# Main_board.net
KiCad netlist of a schematic drawn in EAGLE
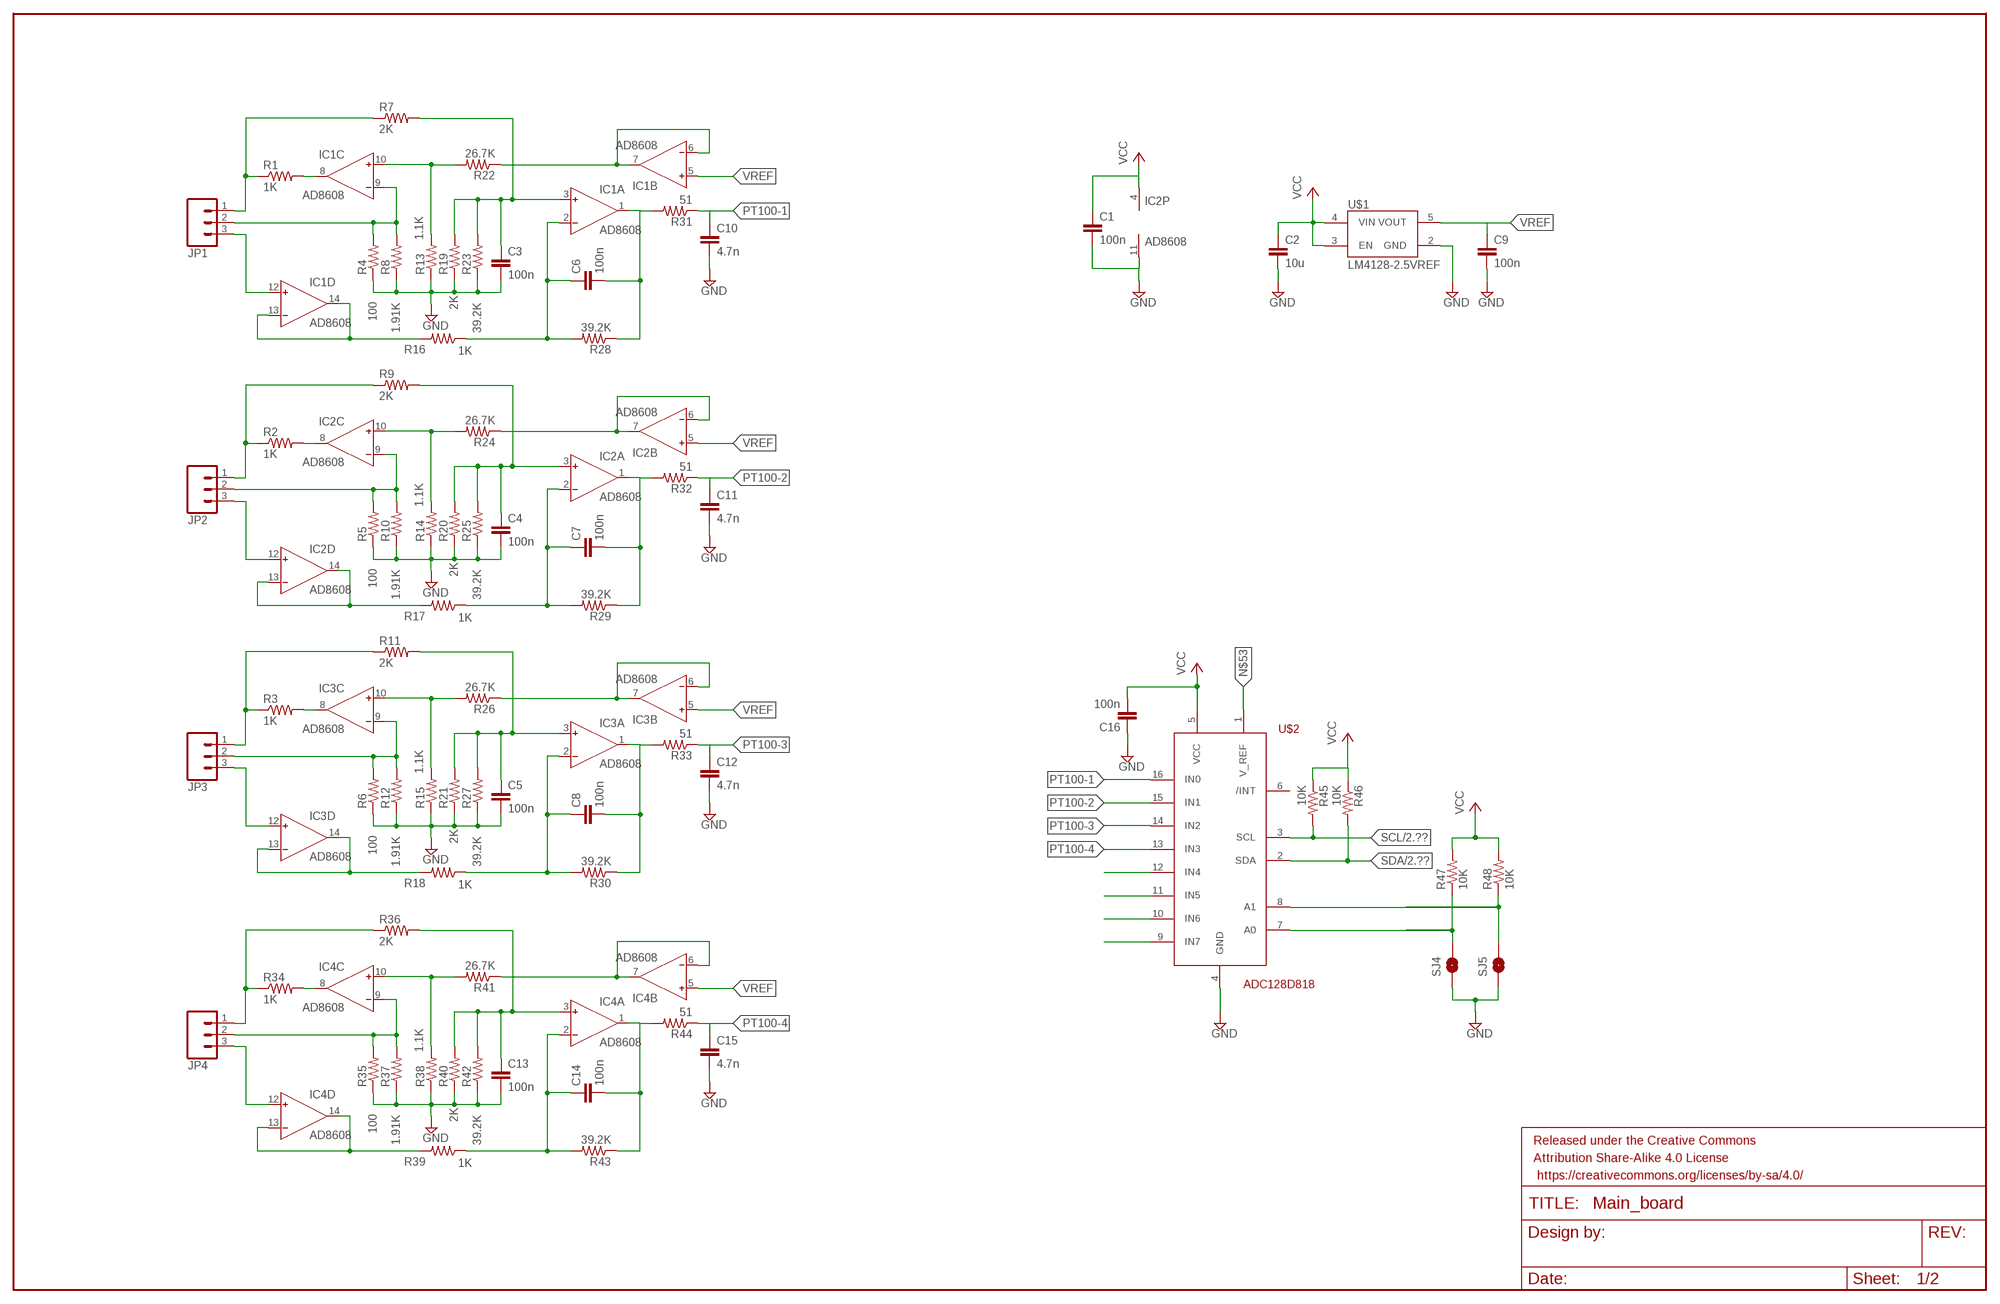
[diagram p0: schematic, sheet 1]
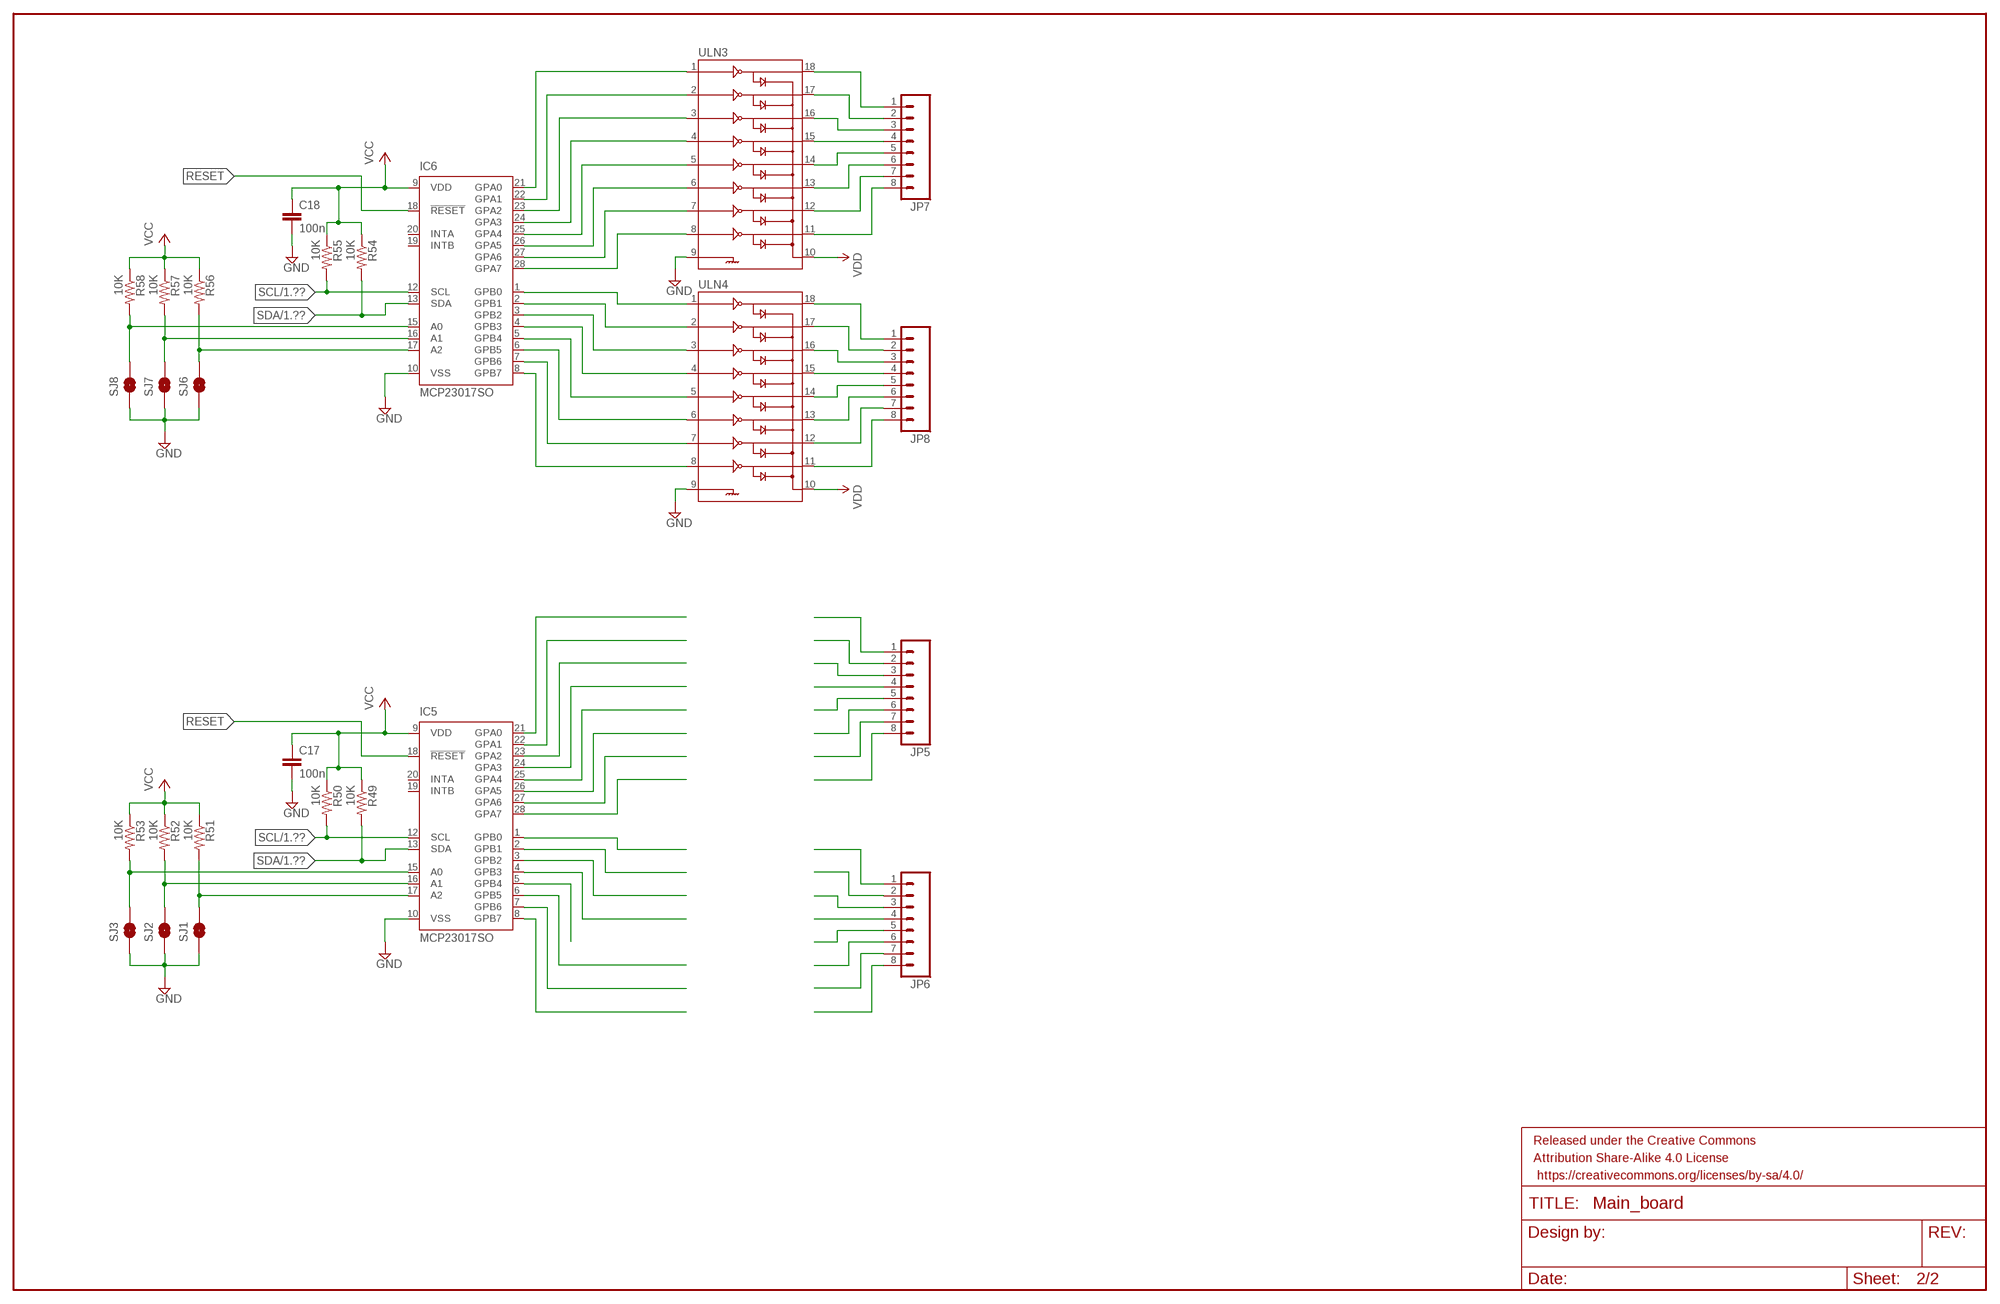
[diagram p1: schematic, sheet 2]

(export (version "E")
  (design (tool "Eeschema 10.0.6"))
  (components
    (comp (ref "C1")
      (value "100n")
      (footprint "eagle-import:0805")
      (libsource (lib "eagle-import") (part "CAP0805"))
    )
    (comp (ref "C2")
      (value "10u")
      (footprint "eagle-import:0805")
      (libsource (lib "eagle-import") (part "CAP0805"))
    )
    (comp (ref "C3")
      (value "100n")
      (footprint "eagle-import:0805")
      (libsource (lib "eagle-import") (part "CAP0805"))
    )
    (comp (ref "C4")
      (value "100n")
      (footprint "eagle-import:0805")
      (libsource (lib "eagle-import") (part "CAP0805"))
    )
    (comp (ref "C5")
      (value "100n")
      (footprint "eagle-import:0805")
      (libsource (lib "eagle-import") (part "CAP0805"))
    )
    (comp (ref "C6")
      (value "100n")
      (footprint "eagle-import:0805")
      (libsource (lib "eagle-import") (part "CAP0805"))
    )
    (comp (ref "C7")
      (value "100n")
      (footprint "eagle-import:0805")
      (libsource (lib "eagle-import") (part "CAP0805"))
    )
    (comp (ref "C8")
      (value "100n")
      (footprint "eagle-import:0805")
      (libsource (lib "eagle-import") (part "CAP0805"))
    )
    (comp (ref "C9")
      (value "100n")
      (footprint "eagle-import:0805")
      (libsource (lib "eagle-import") (part "CAP0805"))
    )
    (comp (ref "C10")
      (value "4.7n")
      (footprint "eagle-import:0805")
      (libsource (lib "eagle-import") (part "CAP0805"))
    )
    (comp (ref "C11")
      (value "4.7n")
      (footprint "eagle-import:0805")
      (libsource (lib "eagle-import") (part "CAP0805"))
    )
    (comp (ref "C12")
      (value "4.7n")
      (footprint "eagle-import:0805")
      (libsource (lib "eagle-import") (part "CAP0805"))
    )
    (comp (ref "C13")
      (value "100n")
      (footprint "eagle-import:0805")
      (libsource (lib "eagle-import") (part "CAP0805"))
    )
    (comp (ref "C14")
      (value "100n")
      (footprint "eagle-import:0805")
      (libsource (lib "eagle-import") (part "CAP0805"))
    )
    (comp (ref "C15")
      (value "4.7n")
      (footprint "eagle-import:0805")
      (libsource (lib "eagle-import") (part "CAP0805"))
    )
    (comp (ref "C16")
      (value "100n")
      (footprint "eagle-import:0805")
      (libsource (lib "eagle-import") (part "CAP0805"))
    )
    (comp (ref "FRAME1")
      (value "FRAME-LEDGER")
      (footprint "eagle-import:CREATIVE_COMMONS")
      (libsource (lib "eagle-import") (part "FRAME-LEDGER"))
    )
    (comp (ref "IC1")
      (value "AD8608")
      (footprint "eagle-import:SO14")
      (fields (field (name "MPN") "AD8609ARZ"))
      (libsource (lib "eagle-import") (part "AD8609R"))
    )
    (comp (ref "IC2")
      (value "AD8608")
      (footprint "eagle-import:SO14")
      (fields (field (name "MPN") "AD8609ARZ"))
      (libsource (lib "eagle-import") (part "AD8609R"))
    )
    (comp (ref "IC3")
      (value "AD8608")
      (footprint "eagle-import:SO14")
      (fields (field (name "MPN") "AD8609ARZ"))
      (libsource (lib "eagle-import") (part "AD8609R"))
    )
    (comp (ref "IC4")
      (value "AD8608")
      (footprint "eagle-import:SO14")
      (fields (field (name "MPN") "AD8609ARZ"))
      (libsource (lib "eagle-import") (part "AD8609R"))
    )
    (comp (ref "JP1")
      (value "M03SCREW")
      (footprint "eagle-import:SCREWTERMINAL-3.5MM-3")
      (libsource (lib "eagle-import") (part "M03SCREW"))
    )
    (comp (ref "JP2")
      (value "M03SCREW")
      (footprint "eagle-import:SCREWTERMINAL-3.5MM-3")
      (libsource (lib "eagle-import") (part "M03SCREW"))
    )
    (comp (ref "JP3")
      (value "M03SCREW")
      (footprint "eagle-import:SCREWTERMINAL-3.5MM-3")
      (libsource (lib "eagle-import") (part "M03SCREW"))
    )
    (comp (ref "JP4")
      (value "M03SCREW")
      (footprint "eagle-import:SCREWTERMINAL-3.5MM-3")
      (libsource (lib "eagle-import") (part "M03SCREW"))
    )
    (comp (ref "R1")
      (value "1K")
      (footprint "eagle-import:0805")
      (libsource (lib "eagle-import") (part "RESISTOR0805-RES"))
    )
    (comp (ref "R2")
      (value "1K")
      (footprint "eagle-import:0805")
      (libsource (lib "eagle-import") (part "RESISTOR0805-RES"))
    )
    (comp (ref "R3")
      (value "1K")
      (footprint "eagle-import:0805")
      (libsource (lib "eagle-import") (part "RESISTOR0805-RES"))
    )
    (comp (ref "R4")
      (value "100")
      (footprint "eagle-import:0805")
      (libsource (lib "eagle-import") (part "RESISTOR0805-RES"))
    )
    (comp (ref "R5")
      (value "100")
      (footprint "eagle-import:0805")
      (libsource (lib "eagle-import") (part "RESISTOR0805-RES"))
    )
    (comp (ref "R6")
      (value "100")
      (footprint "eagle-import:0805")
      (libsource (lib "eagle-import") (part "RESISTOR0805-RES"))
    )
    (comp (ref "R7")
      (value "2K")
      (footprint "eagle-import:0805")
      (libsource (lib "eagle-import") (part "RESISTOR0805-RES"))
    )
    (comp (ref "R8")
      (value "1.91K")
      (footprint "eagle-import:0805")
      (libsource (lib "eagle-import") (part "RESISTOR0805-RES"))
    )
    (comp (ref "R9")
      (value "2K")
      (footprint "eagle-import:0805")
      (libsource (lib "eagle-import") (part "RESISTOR0805-RES"))
    )
    (comp (ref "R10")
      (value "1.91K")
      (footprint "eagle-import:0805")
      (libsource (lib "eagle-import") (part "RESISTOR0805-RES"))
    )
    (comp (ref "R11")
      (value "2K")
      (footprint "eagle-import:0805")
      (libsource (lib "eagle-import") (part "RESISTOR0805-RES"))
    )
    (comp (ref "R12")
      (value "1.91K")
      (footprint "eagle-import:0805")
      (libsource (lib "eagle-import") (part "RESISTOR0805-RES"))
    )
    (comp (ref "R13")
      (value "1.1K")
      (footprint "eagle-import:0805")
      (libsource (lib "eagle-import") (part "RESISTOR0805-RES"))
    )
    (comp (ref "R14")
      (value "1.1K")
      (footprint "eagle-import:0805")
      (libsource (lib "eagle-import") (part "RESISTOR0805-RES"))
    )
    (comp (ref "R15")
      (value "1.1K")
      (footprint "eagle-import:0805")
      (libsource (lib "eagle-import") (part "RESISTOR0805-RES"))
    )
    (comp (ref "R16")
      (value "1K")
      (footprint "eagle-import:0805")
      (libsource (lib "eagle-import") (part "RESISTOR0805-RES"))
    )
    (comp (ref "R17")
      (value "1K")
      (footprint "eagle-import:0805")
      (libsource (lib "eagle-import") (part "RESISTOR0805-RES"))
    )
    (comp (ref "R18")
      (value "1K")
      (footprint "eagle-import:0805")
      (libsource (lib "eagle-import") (part "RESISTOR0805-RES"))
    )
    (comp (ref "R19")
      (value "2K")
      (footprint "eagle-import:0805")
      (libsource (lib "eagle-import") (part "RESISTOR0805-RES"))
    )
    (comp (ref "R20")
      (value "2K")
      (footprint "eagle-import:0805")
      (libsource (lib "eagle-import") (part "RESISTOR0805-RES"))
    )
    (comp (ref "R21")
      (value "2K")
      (footprint "eagle-import:0805")
      (libsource (lib "eagle-import") (part "RESISTOR0805-RES"))
    )
    (comp (ref "R22")
      (value "26.7K")
      (footprint "eagle-import:0805")
      (libsource (lib "eagle-import") (part "RESISTOR0805-RES"))
    )
    (comp (ref "R23")
      (value "39.2K")
      (footprint "eagle-import:0805")
      (libsource (lib "eagle-import") (part "RESISTOR0805-RES"))
    )
    (comp (ref "R24")
      (value "26.7K")
      (footprint "eagle-import:0805")
      (libsource (lib "eagle-import") (part "RESISTOR0805-RES"))
    )
    (comp (ref "R25")
      (value "39.2K")
      (footprint "eagle-import:0805")
      (libsource (lib "eagle-import") (part "RESISTOR0805-RES"))
    )
    (comp (ref "R26")
      (value "26.7K")
      (footprint "eagle-import:0805")
      (libsource (lib "eagle-import") (part "RESISTOR0805-RES"))
    )
    (comp (ref "R27")
      (value "39.2K")
      (footprint "eagle-import:0805")
      (libsource (lib "eagle-import") (part "RESISTOR0805-RES"))
    )
    (comp (ref "R28")
      (value "39.2K")
      (footprint "eagle-import:0805")
      (libsource (lib "eagle-import") (part "RESISTOR0805-RES"))
    )
    (comp (ref "R29")
      (value "39.2K")
      (footprint "eagle-import:0805")
      (libsource (lib "eagle-import") (part "RESISTOR0805-RES"))
    )
    (comp (ref "R30")
      (value "39.2K")
      (footprint "eagle-import:0805")
      (libsource (lib "eagle-import") (part "RESISTOR0805-RES"))
    )
    (comp (ref "R31")
      (value "51")
      (footprint "eagle-import:0805")
      (libsource (lib "eagle-import") (part "RESISTOR0805-RES"))
    )
    (comp (ref "R32")
      (value "51")
      (footprint "eagle-import:0805")
      (libsource (lib "eagle-import") (part "RESISTOR0805-RES"))
    )
    (comp (ref "R33")
      (value "51")
      (footprint "eagle-import:0805")
      (libsource (lib "eagle-import") (part "RESISTOR0805-RES"))
    )
    (comp (ref "R34")
      (value "1K")
      (footprint "eagle-import:0805")
      (libsource (lib "eagle-import") (part "RESISTOR0805-RES"))
    )
    (comp (ref "R35")
      (value "100")
      (footprint "eagle-import:0805")
      (libsource (lib "eagle-import") (part "RESISTOR0805-RES"))
    )
    (comp (ref "R36")
      (value "2K")
      (footprint "eagle-import:0805")
      (libsource (lib "eagle-import") (part "RESISTOR0805-RES"))
    )
    (comp (ref "R37")
      (value "1.91K")
      (footprint "eagle-import:0805")
      (libsource (lib "eagle-import") (part "RESISTOR0805-RES"))
    )
    (comp (ref "R38")
      (value "1.1K")
      (footprint "eagle-import:0805")
      (libsource (lib "eagle-import") (part "RESISTOR0805-RES"))
    )
    (comp (ref "R39")
      (value "1K")
      (footprint "eagle-import:0805")
      (libsource (lib "eagle-import") (part "RESISTOR0805-RES"))
    )
    (comp (ref "R40")
      (value "2K")
      (footprint "eagle-import:0805")
      (libsource (lib "eagle-import") (part "RESISTOR0805-RES"))
    )
    (comp (ref "R41")
      (value "26.7K")
      (footprint "eagle-import:0805")
      (libsource (lib "eagle-import") (part "RESISTOR0805-RES"))
    )
    (comp (ref "R42")
      (value "39.2K")
      (footprint "eagle-import:0805")
      (libsource (lib "eagle-import") (part "RESISTOR0805-RES"))
    )
    (comp (ref "R43")
      (value "39.2K")
      (footprint "eagle-import:0805")
      (libsource (lib "eagle-import") (part "RESISTOR0805-RES"))
    )
    (comp (ref "R44")
      (value "51")
      (footprint "eagle-import:0805")
      (libsource (lib "eagle-import") (part "RESISTOR0805-RES"))
    )
    (comp (ref "R45")
      (value "10K")
      (footprint "eagle-import:0805")
      (libsource (lib "eagle-import") (part "RESISTOR0805-RES"))
    )
    (comp (ref "R46")
      (value "10K")
      (footprint "eagle-import:0805")
      (libsource (lib "eagle-import") (part "RESISTOR0805-RES"))
    )
    (comp (ref "R47")
      (value "10K")
      (footprint "eagle-import:0805")
      (libsource (lib "eagle-import") (part "RESISTOR0805-RES"))
    )
    (comp (ref "R48")
      (value "10K")
      (footprint "eagle-import:0805")
      (libsource (lib "eagle-import") (part "RESISTOR0805-RES"))
    )
    (comp (ref "SJ4")
      (value "SOLDERJUMPERNC")
      (footprint "eagle-import:SJ_2S")
      (libsource (lib "eagle-import") (part "SOLDERJUMPERNC"))
    )
    (comp (ref "SJ5")
      (value "SOLDERJUMPERNC")
      (footprint "eagle-import:SJ_2S")
      (libsource (lib "eagle-import") (part "SOLDERJUMPERNC"))
    )
    (comp (ref "U$1")
      (value "LM4128-2.5VREF")
      (footprint "eagle-import:SOT23-5")
      (libsource (lib "eagle-import") (part "LM4128-2.5VREF"))
    )
    (comp (ref "U$2")
      (value "ADC128D818")
      (footprint "eagle-import:SSOP16")
      (libsource (lib "eagle-import") (part "ADC128D818"))
    )
    (comp (ref "C17")
      (value "100n")
      (footprint "eagle-import:0805")
      (libsource (lib "eagle-import") (part "CAP0805"))
    )
    (comp (ref "C18")
      (value "100n")
      (footprint "eagle-import:0805")
      (libsource (lib "eagle-import") (part "CAP0805"))
    )
    (comp (ref "FRAME2")
      (value "FRAME-LEDGER")
      (footprint "eagle-import:CREATIVE_COMMONS")
      (libsource (lib "eagle-import") (part "FRAME-LEDGER"))
    )
    (comp (ref "IC5")
      (value "MCP23017SO")
      (footprint "eagle-import:SO28W")
      (fields (field (name "MF") "MICROCHIP") (field (name "MPN") "MCP23017-E/SO"))
      (libsource (lib "eagle-import") (part "MCP23017SO"))
    )
    (comp (ref "IC6")
      (value "MCP23017SO")
      (footprint "eagle-import:SO28W")
      (fields (field (name "MF") "MICROCHIP") (field (name "MPN") "MCP23017-E/SO"))
      (libsource (lib "eagle-import") (part "MCP23017SO"))
    )
    (comp (ref "JP5")
      (value "M083.5MM-8")
      (footprint "eagle-import:SCREWTERMINAL-3.5MM-8")
      (libsource (lib "eagle-import") (part "M083.5MM-8"))
    )
    (comp (ref "JP6")
      (value "M083.5MM-8")
      (footprint "eagle-import:SCREWTERMINAL-3.5MM-8")
      (libsource (lib "eagle-import") (part "M083.5MM-8"))
    )
    (comp (ref "JP7")
      (value "M083.5MM-8")
      (footprint "eagle-import:SCREWTERMINAL-3.5MM-8")
      (libsource (lib "eagle-import") (part "M083.5MM-8"))
    )
    (comp (ref "JP8")
      (value "M083.5MM-8")
      (footprint "eagle-import:SCREWTERMINAL-3.5MM-8")
      (libsource (lib "eagle-import") (part "M083.5MM-8"))
    )
    (comp (ref "R49")
      (value "10K")
      (footprint "eagle-import:0805")
      (libsource (lib "eagle-import") (part "RESISTOR0805-RES"))
    )
    (comp (ref "R50")
      (value "10K")
      (footprint "eagle-import:0805")
      (libsource (lib "eagle-import") (part "RESISTOR0805-RES"))
    )
    (comp (ref "R51")
      (value "10K")
      (footprint "eagle-import:0805")
      (libsource (lib "eagle-import") (part "RESISTOR0805-RES"))
    )
    (comp (ref "R52")
      (value "10K")
      (footprint "eagle-import:0805")
      (libsource (lib "eagle-import") (part "RESISTOR0805-RES"))
    )
    (comp (ref "R53")
      (value "10K")
      (footprint "eagle-import:0805")
      (libsource (lib "eagle-import") (part "RESISTOR0805-RES"))
    )
    (comp (ref "R54")
      (value "10K")
      (footprint "eagle-import:0805")
      (libsource (lib "eagle-import") (part "RESISTOR0805-RES"))
    )
    (comp (ref "R55")
      (value "10K")
      (footprint "eagle-import:0805")
      (libsource (lib "eagle-import") (part "RESISTOR0805-RES"))
    )
    (comp (ref "R56")
      (value "10K")
      (footprint "eagle-import:0805")
      (libsource (lib "eagle-import") (part "RESISTOR0805-RES"))
    )
    (comp (ref "R57")
      (value "10K")
      (footprint "eagle-import:0805")
      (libsource (lib "eagle-import") (part "RESISTOR0805-RES"))
    )
    (comp (ref "R58")
      (value "10K")
      (footprint "eagle-import:0805")
      (libsource (lib "eagle-import") (part "RESISTOR0805-RES"))
    )
    (comp (ref "SJ1")
      (value "SOLDERJUMPERNC")
      (footprint "eagle-import:SJ_2S")
      (libsource (lib "eagle-import") (part "SOLDERJUMPERNC"))
    )
    (comp (ref "SJ2")
      (value "SOLDERJUMPERNC")
      (footprint "eagle-import:SJ_2S")
      (libsource (lib "eagle-import") (part "SOLDERJUMPERNC"))
    )
    (comp (ref "SJ3")
      (value "SOLDERJUMPERNC")
      (footprint "eagle-import:SJ_2S")
      (libsource (lib "eagle-import") (part "SOLDERJUMPERNC"))
    )
    (comp (ref "SJ6")
      (value "SOLDERJUMPERNC")
      (footprint "eagle-import:SJ_2S")
      (libsource (lib "eagle-import") (part "SOLDERJUMPERNC"))
    )
    (comp (ref "SJ7")
      (value "SOLDERJUMPERNC")
      (footprint "eagle-import:SJ_2S")
      (libsource (lib "eagle-import") (part "SOLDERJUMPERNC"))
    )
    (comp (ref "SJ8")
      (value "SOLDERJUMPERNC")
      (footprint "eagle-import:SJ_2S")
      (libsource (lib "eagle-import") (part "SOLDERJUMPERNC"))
    )
    (comp (ref "ULN3")
      (value "ULN2803SOIC")
      (footprint "eagle-import:SO018")
      (libsource (lib "eagle-import") (part "ULN2803SOIC"))
    )
    (comp (ref "ULN4")
      (value "ULN2803SOIC")
      (footprint "eagle-import:SO018")
      (libsource (lib "eagle-import") (part "ULN2803SOIC"))
    )
  )
  (nets
    (net (code "1") (name "GND") (class "Default")
      (node (ref "C1") (pin "2") (pinfunction "2_2") (pintype "passive"))
      (node (ref "C10") (pin "2") (pinfunction "2_2") (pintype "passive"))
      (node (ref "C11") (pin "2") (pinfunction "2_2") (pintype "passive"))
      (node (ref "C12") (pin "2") (pinfunction "2_2") (pintype "passive"))
      (node (ref "C13") (pin "2") (pinfunction "2_2") (pintype "passive"))
      (node (ref "C15") (pin "2") (pinfunction "2_2") (pintype "passive"))
      (node (ref "C16") (pin "1") (pinfunction "1_1") (pintype "passive"))
      (node (ref "C17") (pin "2") (pinfunction "2_2") (pintype "passive"))
      (node (ref "C18") (pin "2") (pinfunction "2_2") (pintype "passive"))
      (node (ref "C2") (pin "2") (pinfunction "2_2") (pintype "passive"))
      (node (ref "C3") (pin "2") (pinfunction "2_2") (pintype "passive"))
      (node (ref "C4") (pin "2") (pinfunction "2_2") (pintype "passive"))
      (node (ref "C5") (pin "2") (pinfunction "2_2") (pintype "passive"))
      (node (ref "C9") (pin "2") (pinfunction "2_2") (pintype "passive"))
      (node (ref "IC2") (pin "11") (pinfunction "V-_11") (pintype "power_in"))
      (node (ref "IC5") (pin "10") (pinfunction "VSS_10") (pintype "power_in"))
      (node (ref "IC6") (pin "10") (pinfunction "VSS_10") (pintype "power_in"))
      (node (ref "R10") (pin "1") (pinfunction "1_1") (pintype "passive"))
      (node (ref "R12") (pin "1") (pinfunction "1_1") (pintype "passive"))
      (node (ref "R13") (pin "1") (pinfunction "1_1") (pintype "passive"))
      (node (ref "R14") (pin "1") (pinfunction "1_1") (pintype "passive"))
      (node (ref "R15") (pin "1") (pinfunction "1_1") (pintype "passive"))
      (node (ref "R19") (pin "1") (pinfunction "1_1") (pintype "passive"))
      (node (ref "R20") (pin "1") (pinfunction "1_1") (pintype "passive"))
      (node (ref "R21") (pin "1") (pinfunction "1_1") (pintype "passive"))
      (node (ref "R23") (pin "1") (pinfunction "1_1") (pintype "passive"))
      (node (ref "R25") (pin "1") (pinfunction "1_1") (pintype "passive"))
      (node (ref "R27") (pin "1") (pinfunction "1_1") (pintype "passive"))
      (node (ref "R35") (pin "1") (pinfunction "1_1") (pintype "passive"))
      (node (ref "R37") (pin "1") (pinfunction "1_1") (pintype "passive"))
      (node (ref "R38") (pin "1") (pinfunction "1_1") (pintype "passive"))
      (node (ref "R4") (pin "1") (pinfunction "1_1") (pintype "passive"))
      (node (ref "R40") (pin "1") (pinfunction "1_1") (pintype "passive"))
      (node (ref "R42") (pin "1") (pinfunction "1_1") (pintype "passive"))
      (node (ref "R5") (pin "1") (pinfunction "1_1") (pintype "passive"))
      (node (ref "R6") (pin "1") (pinfunction "1_1") (pintype "passive"))
      (node (ref "R8") (pin "1") (pinfunction "1_1") (pintype "passive"))
      (node (ref "SJ1") (pin "1") (pinfunction "1_1") (pintype "passive"))
      (node (ref "SJ2") (pin "1") (pinfunction "1_1") (pintype "passive"))
      (node (ref "SJ3") (pin "1") (pinfunction "1_1") (pintype "passive"))
      (node (ref "SJ4") (pin "1") (pinfunction "1_1") (pintype "passive"))
      (node (ref "SJ5") (pin "1") (pinfunction "1_1") (pintype "passive"))
      (node (ref "SJ6") (pin "1") (pinfunction "1_1") (pintype "passive"))
      (node (ref "SJ7") (pin "1") (pinfunction "1_1") (pintype "passive"))
      (node (ref "SJ8") (pin "1") (pinfunction "1_1") (pintype "passive"))
      (node (ref "U$1") (pin "2") (pinfunction "GND_2") (pintype "bidirectional"))
      (node (ref "U$2") (pin "4") (pinfunction "GND_4") (pintype "power_in"))
      (node (ref "ULN3") (pin "9") (pinfunction "9_9") (pintype "bidirectional"))
      (node (ref "ULN4") (pin "9") (pinfunction "9_9") (pintype "bidirectional"))
    )
    (net (code "2") (name "N$53") (class "Default")
      (node (ref "U$2") (pin "1") (pinfunction "V_REF_1") (pintype "input"))
    )
    (net (code "3") (name "Net-(IC1A-IN+)") (class "Default")
      (node (ref "C3") (pin "1") (pinfunction "1_1") (pintype "passive"))
      (node (ref "IC1") (pin "3") (pinfunction "IN+_3") (pintype "input"))
      (node (ref "R19") (pin "2") (pinfunction "2_2") (pintype "passive"))
      (node (ref "R23") (pin "2") (pinfunction "2_2") (pintype "passive"))
      (node (ref "R7") (pin "2") (pinfunction "2_2") (pintype "passive"))
    )
    (net (code "4") (name "Net-(IC1A-IN-)") (class "Default")
      (node (ref "C6") (pin "1") (pinfunction "1_1") (pintype "passive"))
      (node (ref "IC1") (pin "2") (pinfunction "IN-_2") (pintype "input"))
      (node (ref "R16") (pin "1") (pinfunction "1_1") (pintype "passive"))
      (node (ref "R28") (pin "2") (pinfunction "2_2") (pintype "passive"))
    )
    (net (code "5") (name "Net-(IC1A-OUT)") (class "Default")
      (node (ref "C6") (pin "2") (pinfunction "2_2") (pintype "passive"))
      (node (ref "IC1") (pin "1") (pinfunction "OUT_1") (pintype "output"))
      (node (ref "R28") (pin "1") (pinfunction "1_1") (pintype "passive"))
      (node (ref "R31") (pin "2") (pinfunction "2_2") (pintype "passive"))
    )
    (net (code "6") (name "Net-(IC1B-IN-)") (class "Default")
      (node (ref "IC1") (pin "6") (pinfunction "IN-_6") (pintype "input"))
      (node (ref "IC1") (pin "7") (pinfunction "OUT_7") (pintype "output"))
      (node (ref "R22") (pin "1") (pinfunction "1_1") (pintype "passive"))
    )
    (net (code "7") (name "Net-(IC1C-IN+)") (class "Default")
      (node (ref "IC1") (pin "10") (pinfunction "IN+_10") (pintype "input"))
      (node (ref "R13") (pin "2") (pinfunction "2_2") (pintype "passive"))
      (node (ref "R22") (pin "2") (pinfunction "2_2") (pintype "passive"))
    )
    (net (code "8") (name "Net-(IC1C-IN-)") (class "Default")
      (node (ref "IC1") (pin "9") (pinfunction "IN-_9") (pintype "input"))
      (node (ref "JP1") (pin "2") (pinfunction "2_2") (pintype "passive"))
      (node (ref "R4") (pin "2") (pinfunction "2_2") (pintype "passive"))
      (node (ref "R8") (pin "2") (pinfunction "2_2") (pintype "passive"))
    )
    (net (code "9") (name "Net-(IC1C-OUT)") (class "Default")
      (node (ref "IC1") (pin "8") (pinfunction "OUT_8") (pintype "output"))
      (node (ref "R1") (pin "2") (pinfunction "2_2") (pintype "passive"))
    )
    (net (code "10") (name "Net-(IC1D-IN+)") (class "Default")
      (node (ref "IC1") (pin "12") (pinfunction "IN+_12") (pintype "input"))
      (node (ref "JP1") (pin "3") (pinfunction "3_3") (pintype "passive"))
    )
    (net (code "11") (name "Net-(IC1D-IN-)") (class "Default")
      (node (ref "IC1") (pin "13") (pinfunction "IN-_13") (pintype "input"))
      (node (ref "IC1") (pin "14") (pinfunction "OUT_14") (pintype "output"))
      (node (ref "R16") (pin "2") (pinfunction "2_2") (pintype "passive"))
    )
    (net (code "12") (name "Net-(IC2A-IN+)") (class "Default")
      (node (ref "C4") (pin "1") (pinfunction "1_1") (pintype "passive"))
      (node (ref "IC2") (pin "3") (pinfunction "IN+_3") (pintype "input"))
      (node (ref "R20") (pin "2") (pinfunction "2_2") (pintype "passive"))
      (node (ref "R25") (pin "2") (pinfunction "2_2") (pintype "passive"))
      (node (ref "R9") (pin "2") (pinfunction "2_2") (pintype "passive"))
    )
    (net (code "13") (name "Net-(IC2A-IN-)") (class "Default")
      (node (ref "C7") (pin "1") (pinfunction "1_1") (pintype "passive"))
      (node (ref "IC2") (pin "2") (pinfunction "IN-_2") (pintype "input"))
      (node (ref "R17") (pin "1") (pinfunction "1_1") (pintype "passive"))
      (node (ref "R29") (pin "2") (pinfunction "2_2") (pintype "passive"))
    )
    (net (code "14") (name "Net-(IC2A-OUT)") (class "Default")
      (node (ref "C7") (pin "2") (pinfunction "2_2") (pintype "passive"))
      (node (ref "IC2") (pin "1") (pinfunction "OUT_1") (pintype "output"))
      (node (ref "R29") (pin "1") (pinfunction "1_1") (pintype "passive"))
      (node (ref "R32") (pin "2") (pinfunction "2_2") (pintype "passive"))
    )
    (net (code "15") (name "Net-(IC2B-IN-)") (class "Default")
      (node (ref "IC2") (pin "6") (pinfunction "IN-_6") (pintype "input"))
      (node (ref "IC2") (pin "7") (pinfunction "OUT_7") (pintype "output"))
      (node (ref "R24") (pin "1") (pinfunction "1_1") (pintype "passive"))
    )
    (net (code "16") (name "Net-(IC2C-IN+)") (class "Default")
      (node (ref "IC2") (pin "10") (pinfunction "IN+_10") (pintype "input"))
      (node (ref "R14") (pin "2") (pinfunction "2_2") (pintype "passive"))
      (node (ref "R24") (pin "2") (pinfunction "2_2") (pintype "passive"))
    )
    (net (code "17") (name "Net-(IC2C-IN-)") (class "Default")
      (node (ref "IC2") (pin "9") (pinfunction "IN-_9") (pintype "input"))
      (node (ref "JP2") (pin "2") (pinfunction "2_2") (pintype "passive"))
      (node (ref "R10") (pin "2") (pinfunction "2_2") (pintype "passive"))
      (node (ref "R5") (pin "2") (pinfunction "2_2") (pintype "passive"))
    )
    (net (code "18") (name "Net-(IC2C-OUT)") (class "Default")
      (node (ref "IC2") (pin "8") (pinfunction "OUT_8") (pintype "output"))
      (node (ref "R2") (pin "2") (pinfunction "2_2") (pintype "passive"))
    )
    (net (code "19") (name "Net-(IC2D-IN+)") (class "Default")
      (node (ref "IC2") (pin "12") (pinfunction "IN+_12") (pintype "input"))
      (node (ref "JP2") (pin "3") (pinfunction "3_3") (pintype "passive"))
    )
    (net (code "20") (name "Net-(IC2D-IN-)") (class "Default")
      (node (ref "IC2") (pin "13") (pinfunction "IN-_13") (pintype "input"))
      (node (ref "IC2") (pin "14") (pinfunction "OUT_14") (pintype "output"))
      (node (ref "R17") (pin "2") (pinfunction "2_2") (pintype "passive"))
    )
    (net (code "21") (name "Net-(IC3A-IN+)") (class "Default")
      (node (ref "C5") (pin "1") (pinfunction "1_1") (pintype "passive"))
      (node (ref "IC3") (pin "3") (pinfunction "IN+_3") (pintype "input"))
      (node (ref "R11") (pin "2") (pinfunction "2_2") (pintype "passive"))
      (node (ref "R21") (pin "2") (pinfunction "2_2") (pintype "passive"))
      (node (ref "R27") (pin "2") (pinfunction "2_2") (pintype "passive"))
    )
    (net (code "22") (name "Net-(IC3A-IN-)") (class "Default")
      (node (ref "C8") (pin "1") (pinfunction "1_1") (pintype "passive"))
      (node (ref "IC3") (pin "2") (pinfunction "IN-_2") (pintype "input"))
      (node (ref "R18") (pin "1") (pinfunction "1_1") (pintype "passive"))
      (node (ref "R30") (pin "2") (pinfunction "2_2") (pintype "passive"))
    )
    (net (code "23") (name "Net-(IC3A-OUT)") (class "Default")
      (node (ref "C8") (pin "2") (pinfunction "2_2") (pintype "passive"))
      (node (ref "IC3") (pin "1") (pinfunction "OUT_1") (pintype "output"))
      (node (ref "R30") (pin "1") (pinfunction "1_1") (pintype "passive"))
      (node (ref "R33") (pin "2") (pinfunction "2_2") (pintype "passive"))
    )
    (net (code "24") (name "Net-(IC3B-IN-)") (class "Default")
      (node (ref "IC3") (pin "6") (pinfunction "IN-_6") (pintype "input"))
      (node (ref "IC3") (pin "7") (pinfunction "OUT_7") (pintype "output"))
      (node (ref "R26") (pin "1") (pinfunction "1_1") (pintype "passive"))
    )
    (net (code "25") (name "Net-(IC3C-IN+)") (class "Default")
      (node (ref "IC3") (pin "10") (pinfunction "IN+_10") (pintype "input"))
      (node (ref "R15") (pin "2") (pinfunction "2_2") (pintype "passive"))
      (node (ref "R26") (pin "2") (pinfunction "2_2") (pintype "passive"))
    )
    (net (code "26") (name "Net-(IC3C-IN-)") (class "Default")
      (node (ref "IC3") (pin "9") (pinfunction "IN-_9") (pintype "input"))
      (node (ref "JP3") (pin "2") (pinfunction "2_2") (pintype "passive"))
      (node (ref "R12") (pin "2") (pinfunction "2_2") (pintype "passive"))
      (node (ref "R6") (pin "2") (pinfunction "2_2") (pintype "passive"))
    )
    (net (code "27") (name "Net-(IC3C-OUT)") (class "Default")
      (node (ref "IC3") (pin "8") (pinfunction "OUT_8") (pintype "output"))
      (node (ref "R3") (pin "2") (pinfunction "2_2") (pintype "passive"))
    )
    (net (code "28") (name "Net-(IC3D-IN+)") (class "Default")
      (node (ref "IC3") (pin "12") (pinfunction "IN+_12") (pintype "input"))
      (node (ref "JP3") (pin "3") (pinfunction "3_3") (pintype "passive"))
    )
    (net (code "29") (name "Net-(IC3D-IN-)") (class "Default")
      (node (ref "IC3") (pin "13") (pinfunction "IN-_13") (pintype "input"))
      (node (ref "IC3") (pin "14") (pinfunction "OUT_14") (pintype "output"))
      (node (ref "R18") (pin "2") (pinfunction "2_2") (pintype "passive"))
    )
    (net (code "30") (name "Net-(IC4A-IN+)") (class "Default")
      (node (ref "C13") (pin "1") (pinfunction "1_1") (pintype "passive"))
      (node (ref "IC4") (pin "3") (pinfunction "IN+_3") (pintype "input"))
      (node (ref "R36") (pin "2") (pinfunction "2_2") (pintype "passive"))
      (node (ref "R40") (pin "2") (pinfunction "2_2") (pintype "passive"))
      (node (ref "R42") (pin "2") (pinfunction "2_2") (pintype "passive"))
    )
    (net (code "31") (name "Net-(IC4A-IN-)") (class "Default")
      (node (ref "C14") (pin "1") (pinfunction "1_1") (pintype "passive"))
      (node (ref "IC4") (pin "2") (pinfunction "IN-_2") (pintype "input"))
      (node (ref "R39") (pin "1") (pinfunction "1_1") (pintype "passive"))
      (node (ref "R43") (pin "2") (pinfunction "2_2") (pintype "passive"))
    )
    (net (code "32") (name "Net-(IC4A-OUT)") (class "Default")
      (node (ref "C14") (pin "2") (pinfunction "2_2") (pintype "passive"))
      (node (ref "IC4") (pin "1") (pinfunction "OUT_1") (pintype "output"))
      (node (ref "R43") (pin "1") (pinfunction "1_1") (pintype "passive"))
      (node (ref "R44") (pin "2") (pinfunction "2_2") (pintype "passive"))
    )
    (net (code "33") (name "Net-(IC4B-IN-)") (class "Default")
      (node (ref "IC4") (pin "6") (pinfunction "IN-_6") (pintype "input"))
      (node (ref "IC4") (pin "7") (pinfunction "OUT_7") (pintype "output"))
      (node (ref "R41") (pin "1") (pinfunction "1_1") (pintype "passive"))
    )
    (net (code "34") (name "Net-(IC4C-IN+)") (class "Default")
      (node (ref "IC4") (pin "10") (pinfunction "IN+_10") (pintype "input"))
      (node (ref "R38") (pin "2") (pinfunction "2_2") (pintype "passive"))
      (node (ref "R41") (pin "2") (pinfunction "2_2") (pintype "passive"))
    )
    (net (code "35") (name "Net-(IC4C-IN-)") (class "Default")
      (node (ref "IC4") (pin "9") (pinfunction "IN-_9") (pintype "input"))
      (node (ref "JP4") (pin "2") (pinfunction "2_2") (pintype "passive"))
      (node (ref "R35") (pin "2") (pinfunction "2_2") (pintype "passive"))
      (node (ref "R37") (pin "2") (pinfunction "2_2") (pintype "passive"))
    )
    (net (code "36") (name "Net-(IC4C-OUT)") (class "Default")
      (node (ref "IC4") (pin "8") (pinfunction "OUT_8") (pintype "output"))
      (node (ref "R34") (pin "2") (pinfunction "2_2") (pintype "passive"))
    )
    (net (code "37") (name "Net-(IC4D-IN+)") (class "Default")
      (node (ref "IC4") (pin "12") (pinfunction "IN+_12") (pintype "input"))
      (node (ref "JP4") (pin "3") (pinfunction "3_3") (pintype "passive"))
    )
    (net (code "38") (name "Net-(IC4D-IN-)") (class "Default")
      (node (ref "IC4") (pin "13") (pinfunction "IN-_13") (pintype "input"))
      (node (ref "IC4") (pin "14") (pinfunction "OUT_14") (pintype "output"))
      (node (ref "R39") (pin "2") (pinfunction "2_2") (pintype "passive"))
    )
    (net (code "39") (name "Net-(IC5-A0)") (class "Default")
      (node (ref "IC5") (pin "15") (pinfunction "A0_15") (pintype "input"))
      (node (ref "R53") (pin "2") (pinfunction "2_2") (pintype "passive"))
      (node (ref "SJ3") (pin "2") (pinfunction "2_2") (pintype "passive"))
    )
    (net (code "40") (name "Net-(IC5-A1)") (class "Default")
      (node (ref "IC5") (pin "16") (pinfunction "A1_16") (pintype "input"))
      (node (ref "R52") (pin "2") (pinfunction "2_2") (pintype "passive"))
      (node (ref "SJ2") (pin "2") (pinfunction "2_2") (pintype "passive"))
    )
    (net (code "41") (name "Net-(IC5-A2)") (class "Default")
      (node (ref "IC5") (pin "17") (pinfunction "A2_17") (pintype "input"))
      (node (ref "R51") (pin "2") (pinfunction "2_2") (pintype "passive"))
      (node (ref "SJ1") (pin "2") (pinfunction "2_2") (pintype "passive"))
    )
    (net (code "42") (name "Net-(IC6-A0)") (class "Default")
      (node (ref "IC6") (pin "15") (pinfunction "A0_15") (pintype "input"))
      (node (ref "R58") (pin "2") (pinfunction "2_2") (pintype "passive"))
      (node (ref "SJ8") (pin "2") (pinfunction "2_2") (pintype "passive"))
    )
    (net (code "43") (name "Net-(IC6-A1)") (class "Default")
      (node (ref "IC6") (pin "16") (pinfunction "A1_16") (pintype "input"))
      (node (ref "R57") (pin "2") (pinfunction "2_2") (pintype "passive"))
      (node (ref "SJ7") (pin "2") (pinfunction "2_2") (pintype "passive"))
    )
    (net (code "44") (name "Net-(IC6-A2)") (class "Default")
      (node (ref "IC6") (pin "17") (pinfunction "A2_17") (pintype "input"))
      (node (ref "R56") (pin "2") (pinfunction "2_2") (pintype "passive"))
      (node (ref "SJ6") (pin "2") (pinfunction "2_2") (pintype "passive"))
    )
    (net (code "45") (name "Net-(IC6-GPA0)") (class "Default")
      (node (ref "IC6") (pin "21") (pinfunction "GPA0_21") (pintype "bidirectional"))
      (node (ref "ULN3") (pin "1") (pinfunction "1_1") (pintype "bidirectional"))
    )
    (net (code "46") (name "Net-(IC6-GPA1)") (class "Default")
      (node (ref "IC6") (pin "22") (pinfunction "GPA1_22") (pintype "bidirectional"))
      (node (ref "ULN3") (pin "2") (pinfunction "2_2") (pintype "bidirectional"))
    )
    (net (code "47") (name "Net-(IC6-GPA2)") (class "Default")
      (node (ref "IC6") (pin "23") (pinfunction "GPA2_23") (pintype "bidirectional"))
      (node (ref "ULN3") (pin "3") (pinfunction "3_3") (pintype "bidirectional"))
    )
    (net (code "48") (name "Net-(IC6-GPA3)") (class "Default")
      (node (ref "IC6") (pin "24") (pinfunction "GPA3_24") (pintype "bidirectional"))
      (node (ref "ULN3") (pin "4") (pinfunction "4_4") (pintype "bidirectional"))
    )
    (net (code "49") (name "Net-(IC6-GPA4)") (class "Default")
      (node (ref "IC6") (pin "25") (pinfunction "GPA4_25") (pintype "bidirectional"))
      (node (ref "ULN3") (pin "5") (pinfunction "5_5") (pintype "bidirectional"))
    )
    (net (code "50") (name "Net-(IC6-GPA5)") (class "Default")
      (node (ref "IC6") (pin "26") (pinfunction "GPA5_26") (pintype "bidirectional"))
      (node (ref "ULN3") (pin "6") (pinfunction "6_6") (pintype "bidirectional"))
    )
    (net (code "51") (name "Net-(IC6-GPA6)") (class "Default")
      (node (ref "IC6") (pin "27") (pinfunction "GPA6_27") (pintype "bidirectional"))
      (node (ref "ULN3") (pin "7") (pinfunction "7_7") (pintype "bidirectional"))
    )
    (net (code "52") (name "Net-(IC6-GPA7)") (class "Default")
      (node (ref "IC6") (pin "28") (pinfunction "GPA7_28") (pintype "bidirectional"))
      (node (ref "ULN3") (pin "8") (pinfunction "8_8") (pintype "bidirectional"))
    )
    (net (code "53") (name "Net-(IC6-GPB0)") (class "Default")
      (node (ref "IC6") (pin "1") (pinfunction "GPB0_1") (pintype "bidirectional"))
      (node (ref "ULN4") (pin "1") (pinfunction "1_1") (pintype "bidirectional"))
    )
    (net (code "54") (name "Net-(IC6-GPB1)") (class "Default")
      (node (ref "IC6") (pin "2") (pinfunction "GPB1_2") (pintype "bidirectional"))
      (node (ref "ULN4") (pin "2") (pinfunction "2_2") (pintype "bidirectional"))
    )
    (net (code "55") (name "Net-(IC6-GPB2)") (class "Default")
      (node (ref "IC6") (pin "3") (pinfunction "GPB2_3") (pintype "bidirectional"))
      (node (ref "ULN4") (pin "3") (pinfunction "3_3") (pintype "bidirectional"))
    )
    (net (code "56") (name "Net-(IC6-GPB3)") (class "Default")
      (node (ref "IC6") (pin "4") (pinfunction "GPB3_4") (pintype "bidirectional"))
      (node (ref "ULN4") (pin "4") (pinfunction "4_4") (pintype "bidirectional"))
    )
    (net (code "57") (name "Net-(IC6-GPB4)") (class "Default")
      (node (ref "IC6") (pin "5") (pinfunction "GPB4_5") (pintype "bidirectional"))
      (node (ref "ULN4") (pin "5") (pinfunction "5_5") (pintype "bidirectional"))
    )
    (net (code "58") (name "Net-(IC6-GPB5)") (class "Default")
      (node (ref "IC6") (pin "6") (pinfunction "GPB5_6") (pintype "bidirectional"))
      (node (ref "ULN4") (pin "6") (pinfunction "6_6") (pintype "bidirectional"))
    )
    (net (code "59") (name "Net-(IC6-GPB6)") (class "Default")
      (node (ref "IC6") (pin "7") (pinfunction "GPB6_7") (pintype "bidirectional"))
      (node (ref "ULN4") (pin "7") (pinfunction "7_7") (pintype "bidirectional"))
    )
    (net (code "60") (name "Net-(IC6-GPB7)") (class "Default")
      (node (ref "IC6") (pin "8") (pinfunction "GPB7_8") (pintype "bidirectional"))
      (node (ref "ULN4") (pin "8") (pinfunction "8_8") (pintype "bidirectional"))
    )
    (net (code "61") (name "Net-(JP1-Pad1)") (class "Default")
      (node (ref "JP1") (pin "1") (pinfunction "1_1") (pintype "passive"))
      (node (ref "R1") (pin "1") (pinfunction "1_1") (pintype "passive"))
      (node (ref "R7") (pin "1") (pinfunction "1_1") (pintype "passive"))
    )
    (net (code "62") (name "Net-(JP2-Pad1)") (class "Default")
      (node (ref "JP2") (pin "1") (pinfunction "1_1") (pintype "passive"))
      (node (ref "R2") (pin "1") (pinfunction "1_1") (pintype "passive"))
      (node (ref "R9") (pin "1") (pinfunction "1_1") (pintype "passive"))
    )
    (net (code "63") (name "Net-(JP3-Pad1)") (class "Default")
      (node (ref "JP3") (pin "1") (pinfunction "1_1") (pintype "passive"))
      (node (ref "R11") (pin "1") (pinfunction "1_1") (pintype "passive"))
      (node (ref "R3") (pin "1") (pinfunction "1_1") (pintype "passive"))
    )
    (net (code "64") (name "Net-(JP4-Pad1)") (class "Default")
      (node (ref "JP4") (pin "1") (pinfunction "1_1") (pintype "passive"))
      (node (ref "R34") (pin "1") (pinfunction "1_1") (pintype "passive"))
      (node (ref "R36") (pin "1") (pinfunction "1_1") (pintype "passive"))
    )
    (net (code "65") (name "Net-(JP7-Pad1)") (class "Default")
      (node (ref "JP7") (pin "1") (pinfunction "1_1") (pintype "passive"))
      (node (ref "ULN3") (pin "18") (pinfunction "18_18") (pintype "bidirectional"))
    )
    (net (code "66") (name "Net-(JP7-Pad2)") (class "Default")
      (node (ref "JP7") (pin "2") (pinfunction "2_2") (pintype "passive"))
      (node (ref "ULN3") (pin "17") (pinfunction "17_17") (pintype "bidirectional"))
    )
    (net (code "67") (name "Net-(JP7-Pad3)") (class "Default")
      (node (ref "JP7") (pin "3") (pinfunction "3_3") (pintype "passive"))
      (node (ref "ULN3") (pin "16") (pinfunction "16_16") (pintype "bidirectional"))
    )
    (net (code "68") (name "Net-(JP7-Pad4)") (class "Default")
      (node (ref "JP7") (pin "4") (pinfunction "4_4") (pintype "passive"))
      (node (ref "ULN3") (pin "15") (pinfunction "15_15") (pintype "bidirectional"))
    )
    (net (code "69") (name "Net-(JP7-Pad5)") (class "Default")
      (node (ref "JP7") (pin "5") (pinfunction "5_5") (pintype "passive"))
      (node (ref "ULN3") (pin "14") (pinfunction "14_14") (pintype "bidirectional"))
    )
    (net (code "70") (name "Net-(JP7-Pad6)") (class "Default")
      (node (ref "JP7") (pin "6") (pinfunction "6_6") (pintype "passive"))
      (node (ref "ULN3") (pin "13") (pinfunction "13_13") (pintype "bidirectional"))
    )
    (net (code "71") (name "Net-(JP7-Pad7)") (class "Default")
      (node (ref "JP7") (pin "7") (pinfunction "7_7") (pintype "passive"))
      (node (ref "ULN3") (pin "12") (pinfunction "12_12") (pintype "bidirectional"))
    )
    (net (code "72") (name "Net-(JP7-Pad8)") (class "Default")
      (node (ref "JP7") (pin "8") (pinfunction "8_8") (pintype "passive"))
      (node (ref "ULN3") (pin "11") (pinfunction "11_11") (pintype "bidirectional"))
    )
    (net (code "73") (name "Net-(JP8-Pad1)") (class "Default")
      (node (ref "JP8") (pin "1") (pinfunction "1_1") (pintype "passive"))
      (node (ref "ULN4") (pin "18") (pinfunction "18_18") (pintype "bidirectional"))
    )
    (net (code "74") (name "Net-(JP8-Pad2)") (class "Default")
      (node (ref "JP8") (pin "2") (pinfunction "2_2") (pintype "passive"))
      (node (ref "ULN4") (pin "17") (pinfunction "17_17") (pintype "bidirectional"))
    )
    (net (code "75") (name "Net-(JP8-Pad3)") (class "Default")
      (node (ref "JP8") (pin "3") (pinfunction "3_3") (pintype "passive"))
      (node (ref "ULN4") (pin "16") (pinfunction "16_16") (pintype "bidirectional"))
    )
    (net (code "76") (name "Net-(JP8-Pad4)") (class "Default")
      (node (ref "JP8") (pin "4") (pinfunction "4_4") (pintype "passive"))
      (node (ref "ULN4") (pin "15") (pinfunction "15_15") (pintype "bidirectional"))
    )
    (net (code "77") (name "Net-(JP8-Pad5)") (class "Default")
      (node (ref "JP8") (pin "5") (pinfunction "5_5") (pintype "passive"))
      (node (ref "ULN4") (pin "14") (pinfunction "14_14") (pintype "bidirectional"))
    )
    (net (code "78") (name "Net-(JP8-Pad6)") (class "Default")
      (node (ref "JP8") (pin "6") (pinfunction "6_6") (pintype "passive"))
      (node (ref "ULN4") (pin "13") (pinfunction "13_13") (pintype "bidirectional"))
    )
    (net (code "79") (name "Net-(JP8-Pad7)") (class "Default")
      (node (ref "JP8") (pin "7") (pinfunction "7_7") (pintype "passive"))
      (node (ref "ULN4") (pin "12") (pinfunction "12_12") (pintype "bidirectional"))
    )
    (net (code "80") (name "Net-(JP8-Pad8)") (class "Default")
      (node (ref "JP8") (pin "8") (pinfunction "8_8") (pintype "passive"))
      (node (ref "ULN4") (pin "11") (pinfunction "11_11") (pintype "bidirectional"))
    )
    (net (code "81") (name "Net-(U$2-A0)") (class "Default")
      (node (ref "R47") (pin "1") (pinfunction "1_1") (pintype "passive"))
      (node (ref "SJ4") (pin "2") (pinfunction "2_2") (pintype "passive"))
      (node (ref "U$2") (pin "7") (pinfunction "A0_7") (pintype "input"))
    )
    (net (code "82") (name "Net-(U$2-A1)") (class "Default")
      (node (ref "R48") (pin "1") (pinfunction "1_1") (pintype "passive"))
      (node (ref "SJ5") (pin "2") (pinfunction "2_2") (pintype "passive"))
      (node (ref "U$2") (pin "8") (pinfunction "A1_8") (pintype "input"))
    )
    (net (code "83") (name "PT100-1") (class "Default")
      (node (ref "C10") (pin "1") (pinfunction "1_1") (pintype "passive"))
      (node (ref "R31") (pin "1") (pinfunction "1_1") (pintype "passive"))
      (node (ref "U$2") (pin "16") (pinfunction "IN0_16") (pintype "input"))
    )
    (net (code "84") (name "PT100-2") (class "Default")
      (node (ref "C11") (pin "1") (pinfunction "1_1") (pintype "passive"))
      (node (ref "R32") (pin "1") (pinfunction "1_1") (pintype "passive"))
      (node (ref "U$2") (pin "15") (pinfunction "IN1_15") (pintype "input"))
    )
    (net (code "85") (name "PT100-3") (class "Default")
      (node (ref "C12") (pin "1") (pinfunction "1_1") (pintype "passive"))
      (node (ref "R33") (pin "1") (pinfunction "1_1") (pintype "passive"))
      (node (ref "U$2") (pin "14") (pinfunction "IN2_14") (pintype "input"))
    )
    (net (code "86") (name "PT100-4") (class "Default")
      (node (ref "C15") (pin "1") (pinfunction "1_1") (pintype "passive"))
      (node (ref "R44") (pin "1") (pinfunction "1_1") (pintype "passive"))
      (node (ref "U$2") (pin "13") (pinfunction "IN3_13") (pintype "input"))
    )
    (net (code "87") (name "RESET") (class "Default")
      (node (ref "IC5") (pin "18") (pinfunction "~{RESET}_18") (pintype "input"))
      (node (ref "IC6") (pin "18") (pinfunction "~{RESET}_18") (pintype "input"))
    )
    (net (code "88") (name "SCL") (class "Default")
      (node (ref "IC5") (pin "12") (pinfunction "SCL_12") (pintype "input"))
      (node (ref "IC6") (pin "12") (pinfunction "SCL_12") (pintype "input"))
      (node (ref "R45") (pin "2") (pinfunction "2_2") (pintype "passive"))
      (node (ref "R50") (pin "2") (pinfunction "2_2") (pintype "passive"))
      (node (ref "R55") (pin "2") (pinfunction "2_2") (pintype "passive"))
      (node (ref "U$2") (pin "3") (pinfunction "SCL_3") (pintype "input"))
    )
    (net (code "89") (name "SDA") (class "Default")
      (node (ref "IC5") (pin "13") (pinfunction "SDA_13") (pintype "bidirectional"))
      (node (ref "IC6") (pin "13") (pinfunction "SDA_13") (pintype "bidirectional"))
      (node (ref "R46") (pin "2") (pinfunction "2_2") (pintype "passive"))
      (node (ref "R49") (pin "2") (pinfunction "2_2") (pintype "passive"))
      (node (ref "R54") (pin "2") (pinfunction "2_2") (pintype "passive"))
      (node (ref "U$2") (pin "2") (pinfunction "SDA_2") (pintype "bidirectional"))
    )
    (net (code "90") (name "VCC") (class "Default")
      (node (ref "C1") (pin "1") (pinfunction "1_1") (pintype "passive"))
      (node (ref "C16") (pin "2") (pinfunction "2_2") (pintype "passive"))
      (node (ref "C17") (pin "1") (pinfunction "1_1") (pintype "passive"))
      (node (ref "C18") (pin "1") (pinfunction "1_1") (pintype "passive"))
      (node (ref "C2") (pin "1") (pinfunction "1_1") (pintype "passive"))
      (node (ref "IC2") (pin "4") (pinfunction "V+_4") (pintype "power_in"))
      (node (ref "IC5") (pin "9") (pinfunction "VDD_9") (pintype "power_in"))
      (node (ref "IC6") (pin "9") (pinfunction "VDD_9") (pintype "power_in"))
      (node (ref "R45") (pin "1") (pinfunction "1_1") (pintype "passive"))
      (node (ref "R46") (pin "1") (pinfunction "1_1") (pintype "passive"))
      (node (ref "R47") (pin "2") (pinfunction "2_2") (pintype "passive"))
      (node (ref "R48") (pin "2") (pinfunction "2_2") (pintype "passive"))
      (node (ref "R49") (pin "1") (pinfunction "1_1") (pintype "passive"))
      (node (ref "R50") (pin "1") (pinfunction "1_1") (pintype "passive"))
      (node (ref "R51") (pin "1") (pinfunction "1_1") (pintype "passive"))
      (node (ref "R52") (pin "1") (pinfunction "1_1") (pintype "passive"))
      (node (ref "R53") (pin "1") (pinfunction "1_1") (pintype "passive"))
      (node (ref "R54") (pin "1") (pinfunction "1_1") (pintype "passive"))
      (node (ref "R55") (pin "1") (pinfunction "1_1") (pintype "passive"))
      (node (ref "R56") (pin "1") (pinfunction "1_1") (pintype "passive"))
      (node (ref "R57") (pin "1") (pinfunction "1_1") (pintype "passive"))
      (node (ref "R58") (pin "1") (pinfunction "1_1") (pintype "passive"))
      (node (ref "U$1") (pin "3") (pinfunction "EN_3") (pintype "bidirectional"))
      (node (ref "U$1") (pin "4") (pinfunction "VIN_4") (pintype "bidirectional"))
      (node (ref "U$2") (pin "5") (pinfunction "VCC_5") (pintype "power_in"))
    )
    (net (code "91") (name "VDD") (class "Default")
      (node (ref "ULN3") (pin "10") (pinfunction "10_10") (pintype "bidirectional"))
      (node (ref "ULN4") (pin "10") (pinfunction "10_10") (pintype "bidirectional"))
    )
    (net (code "92") (name "VREF") (class "Default")
      (node (ref "C9") (pin "1") (pinfunction "1_1") (pintype "passive"))
      (node (ref "IC1") (pin "5") (pinfunction "IN+_5") (pintype "input"))
      (node (ref "IC2") (pin "5") (pinfunction "IN+_5") (pintype "input"))
      (node (ref "IC3") (pin "5") (pinfunction "IN+_5") (pintype "input"))
      (node (ref "IC4") (pin "5") (pinfunction "IN+_5") (pintype "input"))
      (node (ref "U$1") (pin "5") (pinfunction "VOUT_5") (pintype "bidirectional"))
    )
    (net (code "93") (name "unconnected-(IC5-GPA0-Pad21)") (class "Default")
      (node (ref "IC5") (pin "21") (pinfunction "GPA0_21") (pintype "bidirectional"))
    )
    (net (code "94") (name "unconnected-(IC5-GPA1-Pad22)") (class "Default")
      (node (ref "IC5") (pin "22") (pinfunction "GPA1_22") (pintype "bidirectional"))
    )
    (net (code "95") (name "unconnected-(IC5-GPA2-Pad23)") (class "Default")
      (node (ref "IC5") (pin "23") (pinfunction "GPA2_23") (pintype "bidirectional"))
    )
    (net (code "96") (name "unconnected-(IC5-GPA3-Pad24)") (class "Default")
      (node (ref "IC5") (pin "24") (pinfunction "GPA3_24") (pintype "bidirectional"))
    )
    (net (code "97") (name "unconnected-(IC5-GPA4-Pad25)") (class "Default")
      (node (ref "IC5") (pin "25") (pinfunction "GPA4_25") (pintype "bidirectional"))
    )
    (net (code "98") (name "unconnected-(IC5-GPA5-Pad26)") (class "Default")
      (node (ref "IC5") (pin "26") (pinfunction "GPA5_26") (pintype "bidirectional"))
    )
    (net (code "99") (name "unconnected-(IC5-GPA6-Pad27)") (class "Default")
      (node (ref "IC5") (pin "27") (pinfunction "GPA6_27") (pintype "bidirectional"))
    )
    (net (code "100") (name "unconnected-(IC5-GPA7-Pad28)") (class "Default")
      (node (ref "IC5") (pin "28") (pinfunction "GPA7_28") (pintype "bidirectional"))
    )
    (net (code "101") (name "unconnected-(IC5-GPB0-Pad1)") (class "Default")
      (node (ref "IC5") (pin "1") (pinfunction "GPB0_1") (pintype "bidirectional"))
    )
    (net (code "102") (name "unconnected-(IC5-GPB1-Pad2)") (class "Default")
      (node (ref "IC5") (pin "2") (pinfunction "GPB1_2") (pintype "bidirectional"))
    )
    (net (code "103") (name "unconnected-(IC5-GPB2-Pad3)") (class "Default")
      (node (ref "IC5") (pin "3") (pinfunction "GPB2_3") (pintype "bidirectional"))
    )
    (net (code "104") (name "unconnected-(IC5-GPB3-Pad4)") (class "Default")
      (node (ref "IC5") (pin "4") (pinfunction "GPB3_4") (pintype "bidirectional"))
    )
    (net (code "105") (name "unconnected-(IC5-GPB4-Pad5)") (class "Default")
      (node (ref "IC5") (pin "5") (pinfunction "GPB4_5") (pintype "bidirectional"))
    )
    (net (code "106") (name "unconnected-(IC5-GPB5-Pad6)") (class "Default")
      (node (ref "IC5") (pin "6") (pinfunction "GPB5_6") (pintype "bidirectional"))
    )
    (net (code "107") (name "unconnected-(IC5-GPB6-Pad7)") (class "Default")
      (node (ref "IC5") (pin "7") (pinfunction "GPB6_7") (pintype "bidirectional"))
    )
    (net (code "108") (name "unconnected-(IC5-GPB7-Pad8)") (class "Default")
      (node (ref "IC5") (pin "8") (pinfunction "GPB7_8") (pintype "bidirectional"))
    )
    (net (code "109") (name "unconnected-(IC5-INTA-Pad20)") (class "Default")
      (node (ref "IC5") (pin "20") (pinfunction "INTA_20") (pintype "output"))
    )
    (net (code "110") (name "unconnected-(IC5-INTB-Pad19)") (class "Default")
      (node (ref "IC5") (pin "19") (pinfunction "INTB_19") (pintype "output"))
    )
    (net (code "111") (name "unconnected-(IC6-INTA-Pad20)") (class "Default")
      (node (ref "IC6") (pin "20") (pinfunction "INTA_20") (pintype "output"))
    )
    (net (code "112") (name "unconnected-(IC6-INTB-Pad19)") (class "Default")
      (node (ref "IC6") (pin "19") (pinfunction "INTB_19") (pintype "output"))
    )
    (net (code "113") (name "unconnected-(JP5-Pad1)") (class "Default")
      (node (ref "JP5") (pin "1") (pinfunction "1_1") (pintype "passive"))
    )
    (net (code "114") (name "unconnected-(JP5-Pad2)") (class "Default")
      (node (ref "JP5") (pin "2") (pinfunction "2_2") (pintype "passive"))
    )
    (net (code "115") (name "unconnected-(JP5-Pad3)") (class "Default")
      (node (ref "JP5") (pin "3") (pinfunction "3_3") (pintype "passive"))
    )
    (net (code "116") (name "unconnected-(JP5-Pad4)") (class "Default")
      (node (ref "JP5") (pin "4") (pinfunction "4_4") (pintype "passive"))
    )
    (net (code "117") (name "unconnected-(JP5-Pad5)") (class "Default")
      (node (ref "JP5") (pin "5") (pinfunction "5_5") (pintype "passive"))
    )
    (net (code "118") (name "unconnected-(JP5-Pad6)") (class "Default")
      (node (ref "JP5") (pin "6") (pinfunction "6_6") (pintype "passive"))
    )
    (net (code "119") (name "unconnected-(JP5-Pad7)") (class "Default")
      (node (ref "JP5") (pin "7") (pinfunction "7_7") (pintype "passive"))
    )
    (net (code "120") (name "unconnected-(JP5-Pad8)") (class "Default")
      (node (ref "JP5") (pin "8") (pinfunction "8_8") (pintype "passive"))
    )
    (net (code "121") (name "unconnected-(JP6-Pad1)") (class "Default")
      (node (ref "JP6") (pin "1") (pinfunction "1_1") (pintype "passive"))
    )
    (net (code "122") (name "unconnected-(JP6-Pad2)") (class "Default")
      (node (ref "JP6") (pin "2") (pinfunction "2_2") (pintype "passive"))
    )
    (net (code "123") (name "unconnected-(JP6-Pad3)") (class "Default")
      (node (ref "JP6") (pin "3") (pinfunction "3_3") (pintype "passive"))
    )
    (net (code "124") (name "unconnected-(JP6-Pad4)") (class "Default")
      (node (ref "JP6") (pin "4") (pinfunction "4_4") (pintype "passive"))
    )
    (net (code "125") (name "unconnected-(JP6-Pad5)") (class "Default")
      (node (ref "JP6") (pin "5") (pinfunction "5_5") (pintype "passive"))
    )
    (net (code "126") (name "unconnected-(JP6-Pad6)") (class "Default")
      (node (ref "JP6") (pin "6") (pinfunction "6_6") (pintype "passive"))
    )
    (net (code "127") (name "unconnected-(JP6-Pad7)") (class "Default")
      (node (ref "JP6") (pin "7") (pinfunction "7_7") (pintype "passive"))
    )
    (net (code "128") (name "unconnected-(JP6-Pad8)") (class "Default")
      (node (ref "JP6") (pin "8") (pinfunction "8_8") (pintype "passive"))
    )
    (net (code "129") (name "unconnected-(U$2-IN4-Pad12)") (class "Default")
      (node (ref "U$2") (pin "12") (pinfunction "IN4_12") (pintype "input"))
    )
    (net (code "130") (name "unconnected-(U$2-IN5-Pad11)") (class "Default")
      (node (ref "U$2") (pin "11") (pinfunction "IN5_11") (pintype "input"))
    )
    (net (code "131") (name "unconnected-(U$2-IN6-Pad10)") (class "Default")
      (node (ref "U$2") (pin "10") (pinfunction "IN6_10") (pintype "input"))
    )
    (net (code "132") (name "unconnected-(U$2-IN7-Pad9)") (class "Default")
      (node (ref "U$2") (pin "9") (pinfunction "IN7_9") (pintype "input"))
    )
    (net (code "133") (name "unconnected-(U$2-{slash}INT-Pad6)") (class "Default")
      (node (ref "U$2") (pin "6") (pinfunction "/INT_6") (pintype "output"))
    )
  )
)
